# Cal_Laser_Board.net
KiCad netlist of a schematic drawn in Altium Designer
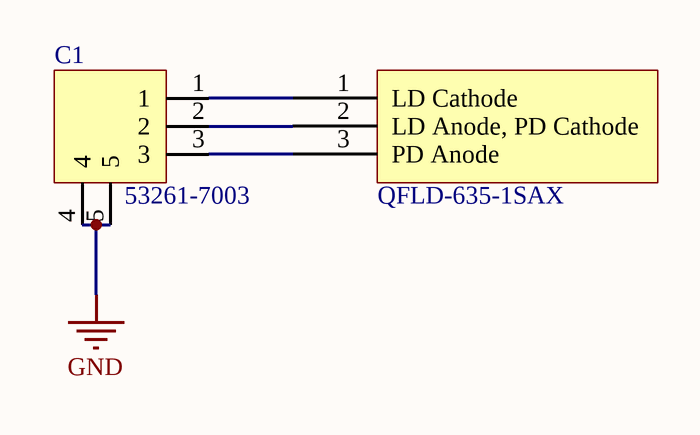
[diagram p0: Cal_Laser_Board.SchDoc]

(export (version "E")
  (design (tool "Eeschema 10.0.6"))
  (components
    (comp (ref "C1")
      (value "53261-7003")
      (footprint "532617003")
      (libsource (lib "Calibration_Laser_Board") (part "53261-7003"))
    )
    (comp (ref "L1")
      (value "QFLD-635-1SAX")
      (footprint "QFLD-635-1SAX")
      (libsource (lib "Calibration_Laser_Board") (part "QFLD-635-1SAX"))
    )
  )
  (nets
    (net (code "1") (name "GND") (class "Default")
      (node (ref "C1") (pin "4") (pinfunction "4_4") (pintype "passive"))
      (node (ref "C1") (pin "5") (pinfunction "5_5") (pintype "passive"))
    )
    (net (code "2") (name "Net-(L1-LD_Anode,_PD_Cathode)") (class "Default")
      (node (ref "C1") (pin "2") (pinfunction "2_2") (pintype "passive"))
      (node (ref "L1") (pin "2") (pinfunction "LD_Anode,_PD_Cathode_2") (pintype "passive"))
    )
    (net (code "3") (name "Net-(L1-LD_Cathode)") (class "Default")
      (node (ref "C1") (pin "1") (pinfunction "1_1") (pintype "passive"))
      (node (ref "L1") (pin "1") (pinfunction "LD_Cathode_1") (pintype "passive"))
    )
    (net (code "4") (name "Net-(L1-PD_Anode)") (class "Default")
      (node (ref "C1") (pin "3") (pinfunction "3_3") (pintype "passive"))
      (node (ref "L1") (pin "3") (pinfunction "PD_Anode_3") (pintype "passive"))
    )
  )
)
